# PIR_Part_V_1.net
KiCad netlist of a schematic drawn in Altium Designer
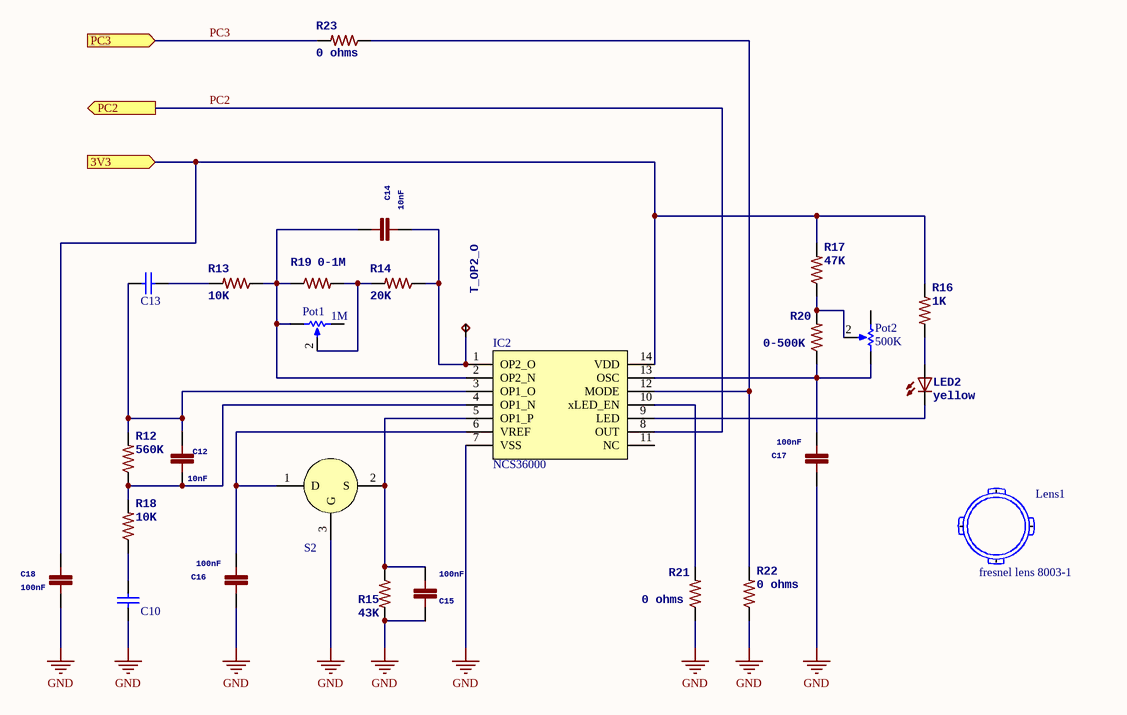
[diagram p0: PIR_Part_V.1.SchDoc]

(export (version "E")
  (design (tool "Eeschema 10.0.6"))
  (components
    (comp (ref "C10")
      (value "33uF")
      (footprint "Axsem-PIR_V.1:C1206")
      (description "C1206")
      (libsource (lib "Axsem-PIR_V.1") (part "C1206"))
    )
    (comp (ref "C12") (value "10nF") (footprint "Axsem-PIR_V.1:C0402") (libsource (lib "") (part "C0402_2")))
    (comp (ref "C13")
      (value "33uF")
      (footprint "Axsem-PIR_V.1:C1206")
      (description "C1206")
      (libsource (lib "Axsem-PIR_V.1") (part "C1206"))
    )
    (comp (ref "C14") (value "10nF") (footprint "Axsem-PIR_V.1:C0402") (libsource (lib "") (part "C0402_1")))
    (comp (ref "C15")
      (value "100nF")
      (footprint "Axsem-PIR_V.1:C0402")
      (libsource (lib "Axsem-PIR_V.1") (part "C0402"))
    )
    (comp (ref "C16") (value "100nF") (footprint "C0402") (libsource (lib "Axsem-PIR_V.1") (part "C0402")))
    (comp (ref "C17") (value "100nF") (footprint "C0402") (libsource (lib "Axsem-PIR_V.1") (part "C0402")))
    (comp (ref "C18")
      (value "100nF")
      (footprint "C0603")
      (description "C0603")
      (libsource (lib "Axsem-PIR_V.1") (part "C0603"))
    )
    (comp (ref "IC2")
      (value "NCS36000")
      (footprint "SOIC127P600X175-14AN")
      (description "PIR sensor")
      (fields (field (name "MANUFACTURER") "ON semiconductor"))
      (libsource (lib "Axsem-PIR_V.1") (part "NCS36000"))
    )
    (comp (ref "LED2")
      (value "yellow")
      (footprint "LED0603 - Y")
      (description "LED0603-Y")
      (libsource (lib "Axsem-PIR_V.1") (part "LED0603 yellow"))
    )
    (comp (ref "Lens1")
      (value "fresnel lens 8003-1")
      (footprint "Axsem-PIR_V.1:Lens")
      (description "Fresnel Lens 8003-1")
      (libsource (lib "Axsem-PIR_V.1") (part "PIR Fresnel Lens 8003-1"))
    )
    (comp (ref "Pot1")
      (value "1M")
      (footprint "Poti-4mm SMD")
      (description "Bourns 3364W SMD 4mm square Trimpot")
      (libsource (lib "Axsem-PIR_V.1") (part "Trimpot SMD"))
    )
    (comp (ref "Pot2")
      (value "500K")
      (footprint "Poti-4mm SMD")
      (description "Bourns 3364W SMD 4mm square Trimpot")
      (libsource (lib "Axsem-PIR_V.1") (part "Trimpot SMD"))
    )
    (comp (ref "R12") (value "560K") (footprint "R0402") (libsource (lib "Axsem-PIR_V.1") (part "R0402")))
    (comp (ref "R13") (value "10K") (footprint "R0402") (libsource (lib "Axsem-PIR_V.1") (part "R0402")))
    (comp (ref "R14") (value "20K") (footprint "R0402") (libsource (lib "Axsem-PIR_V.1") (part "R0402")))
    (comp (ref "R15") (value "43K") (footprint "R0402") (libsource (lib "Axsem-PIR_V.1") (part "R0402")))
    (comp (ref "R16") (value "1K") (footprint "R0402") (libsource (lib "Axsem-PIR_V.1") (part "R0402")))
    (comp (ref "R17") (value "47K") (footprint "R0402") (libsource (lib "Axsem-PIR_V.1") (part "R0402")))
    (comp (ref "R18") (value "10K") (footprint "R0402") (libsource (lib "Axsem-PIR_V.1") (part "R0402")))
    (comp (ref "R19") (value "0-1M") (footprint "R0402") (libsource (lib "Axsem-PIR_V.1") (part "R0402")))
    (comp (ref "R20") (value "0-500K") (footprint "R0402") (libsource (lib "Axsem-PIR_V.1") (part "R0402")))
    (comp (ref "R21") (value "0 ohms") (footprint "R0402") (libsource (lib "Axsem-PIR_V.1") (part "R0402")))
    (comp (ref "R22") (value "0 ohms") (footprint "R0402") (libsource (lib "Axsem-PIR_V.1") (part "R0402")))
    (comp (ref "R23") (value "0 ohms") (footprint "R0402") (libsource (lib "Axsem-PIR_V.1") (part "R0402")))
    (comp (ref "S2")
      (value "D203S")
      (footprint "ONSC-TO-5-3")
      (description "PIR sensor")
      (fields (field (name "MANUFACTURER") "PIR sensor CO.,LTD"))
      (libsource (lib "Axsem-PIR_V.1") (part "D203S PIR sensor"))
    )
    (comp (ref "T_OP2_O")
      (value "TP03")
      (footprint "PIN-03")
      (description "Test pad")
      (libsource (lib "Axsem-PIR_V.1") (part "TP03"))
    )
  )
  (nets
    (net (code "1") (name "/3V3") (class "Default")
      (node (ref "C18") (pin "2") (pinfunction "2_2") (pintype "passive"))
      (node (ref "IC2") (pin "14") (pinfunction "VDD_14") (pintype "passive"))
      (node (ref "R16") (pin "1") (pinfunction "1_1") (pintype "passive"))
      (node (ref "R17") (pin "2") (pinfunction "2_2") (pintype "passive"))
    )
    (net (code "2") (name "/PC2") (class "Default")
      (node (ref "IC2") (pin "8") (pinfunction "OUT_8") (pintype "passive"))
    )
    (net (code "3") (name "/PC3") (class "Default")
      (node (ref "R23") (pin "2") (pinfunction "2_2") (pintype "passive"))
    )
    (net (code "4") (name "GND") (class "Default")
      (node (ref "C10") (pin "1") (pinfunction "1_1") (pintype "passive"))
      (node (ref "C15") (pin "1") (pinfunction "1_1") (pintype "passive"))
      (node (ref "C16") (pin "1") (pinfunction "1_1") (pintype "passive"))
      (node (ref "C17") (pin "1") (pinfunction "1_1") (pintype "passive"))
      (node (ref "C18") (pin "1") (pinfunction "1_1") (pintype "passive"))
      (node (ref "IC2") (pin "7") (pinfunction "VSS_7") (pintype "passive"))
      (node (ref "R15") (pin "2") (pinfunction "2_2") (pintype "passive"))
      (node (ref "R21") (pin "1") (pinfunction "1_1") (pintype "passive"))
      (node (ref "R22") (pin "1") (pinfunction "1_1") (pintype "passive"))
      (node (ref "S2") (pin "3") (pinfunction "G_3") (pintype "passive"))
    )
    (net (code "5") (name "Net-(C10-Pad2)") (class "Default")
      (node (ref "C10") (pin "2") (pinfunction "2_2") (pintype "passive"))
      (node (ref "R18") (pin "1") (pinfunction "1_1") (pintype "passive"))
    )
    (net (code "6") (name "Net-(C13-Pad1)") (class "Default")
      (node (ref "C13") (pin "1") (pinfunction "1_1") (pintype "passive"))
      (node (ref "R13") (pin "2") (pinfunction "2_2") (pintype "passive"))
    )
    (net (code "7") (name "Net-(IC2-LED)") (class "Default")
      (node (ref "IC2") (pin "9") (pinfunction "LED_9") (pintype "passive"))
      (node (ref "LED2") (pin "C") (pinfunction "C_C") (pintype "passive"))
    )
    (net (code "8") (name "Net-(IC2-MODE)") (class "Default")
      (node (ref "IC2") (pin "12") (pinfunction "MODE_12") (pintype "passive"))
      (node (ref "R22") (pin "2") (pinfunction "2_2") (pintype "passive"))
      (node (ref "R23") (pin "1") (pinfunction "1_1") (pintype "passive"))
    )
    (net (code "9") (name "Net-(IC2-OP1_N)") (class "Default")
      (node (ref "C12") (pin "2") (pinfunction "2_2") (pintype "passive"))
      (node (ref "IC2") (pin "4") (pinfunction "OP1_N_4") (pintype "passive"))
      (node (ref "R12") (pin "1") (pinfunction "1_1") (pintype "passive"))
      (node (ref "R18") (pin "2") (pinfunction "2_2") (pintype "passive"))
    )
    (net (code "10") (name "Net-(IC2-OP1_O)") (class "Default")
      (node (ref "C12") (pin "1") (pinfunction "1_1") (pintype "passive"))
      (node (ref "C13") (pin "2") (pinfunction "2_2") (pintype "passive"))
      (node (ref "IC2") (pin "3") (pinfunction "OP1_O_3") (pintype "passive"))
      (node (ref "R12") (pin "2") (pinfunction "2_2") (pintype "passive"))
    )
    (net (code "11") (name "Net-(IC2-OP1_P)") (class "Default")
      (node (ref "C15") (pin "2") (pinfunction "2_2") (pintype "passive"))
      (node (ref "IC2") (pin "5") (pinfunction "OP1_P_5") (pintype "passive"))
      (node (ref "R15") (pin "1") (pinfunction "1_1") (pintype "passive"))
      (node (ref "S2") (pin "2") (pinfunction "S_2") (pintype "passive"))
    )
    (net (code "12") (name "Net-(IC2-OP2_N)") (class "Default")
      (node (ref "C14") (pin "1") (pinfunction "1_1") (pintype "passive"))
      (node (ref "IC2") (pin "2") (pinfunction "OP2_N_2") (pintype "passive"))
      (node (ref "Pot1") (pin "1") (pinfunction "1_1") (pintype "passive"))
      (node (ref "R13") (pin "1") (pinfunction "1_1") (pintype "passive"))
      (node (ref "R19") (pin "1") (pinfunction "1_1") (pintype "passive"))
    )
    (net (code "13") (name "Net-(IC2-OP2_O)") (class "Default")
      (node (ref "C14") (pin "2") (pinfunction "2_2") (pintype "passive"))
      (node (ref "IC2") (pin "1") (pinfunction "OP2_O_1") (pintype "passive"))
      (node (ref "R14") (pin "1") (pinfunction "1_1") (pintype "passive"))
      (node (ref "T_OP2_O") (pin "P$1") (pinfunction "TP_P$1") (pintype "passive"))
    )
    (net (code "14") (name "Net-(IC2-OSC)") (class "Default")
      (node (ref "C17") (pin "2") (pinfunction "2_2") (pintype "passive"))
      (node (ref "IC2") (pin "13") (pinfunction "OSC_13") (pintype "passive"))
      (node (ref "Pot2") (pin "3") (pinfunction "3_3") (pintype "passive"))
      (node (ref "R20") (pin "1") (pinfunction "1_1") (pintype "passive"))
    )
    (net (code "15") (name "Net-(IC2-VREF)") (class "Default")
      (node (ref "C16") (pin "2") (pinfunction "2_2") (pintype "passive"))
      (node (ref "IC2") (pin "6") (pinfunction "VREF_6") (pintype "passive"))
      (node (ref "S2") (pin "1") (pinfunction "D_1") (pintype "passive"))
    )
    (net (code "16") (name "Net-(IC2-xLED_EN)") (class "Default")
      (node (ref "IC2") (pin "10") (pinfunction "xLED_EN_10") (pintype "passive"))
      (node (ref "R21") (pin "2") (pinfunction "2_2") (pintype "passive"))
    )
    (net (code "17") (name "Net-(LED2-PadA)") (class "Default")
      (node (ref "LED2") (pin "A") (pinfunction "A_A") (pintype "passive"))
      (node (ref "R16") (pin "2") (pinfunction "2_2") (pintype "passive"))
    )
    (net (code "18") (name "Net-(Pot1-Pad2)") (class "Default")
      (node (ref "Pot1") (pin "2") (pinfunction "2_2") (pintype "passive"))
      (node (ref "R14") (pin "2") (pinfunction "2_2") (pintype "passive"))
      (node (ref "R19") (pin "2") (pinfunction "2_2") (pintype "passive"))
    )
    (net (code "19") (name "Net-(Pot2-Pad2)") (class "Default")
      (node (ref "Pot2") (pin "2") (pinfunction "2_2") (pintype "passive"))
      (node (ref "R17") (pin "1") (pinfunction "1_1") (pintype "passive"))
      (node (ref "R20") (pin "2") (pinfunction "2_2") (pintype "passive"))
    )
    (net (code "20") (name "unconnected-(IC2-NC-Pad11)") (class "Default")
      (node (ref "IC2") (pin "11") (pinfunction "NC_11") (pintype "passive"))
    )
    (net (code "21") (name "unconnected-(Lens1-PadTab1)") (class "Default")
      (node (ref "Lens1") (pin "Tab1") (pinfunction "Tab1_Tab1") (pintype "passive"))
    )
    (net (code "22") (name "unconnected-(Lens1-PadTab2)") (class "Default")
      (node (ref "Lens1") (pin "Tab2") (pinfunction "Tab2_Tab2") (pintype "passive"))
    )
    (net (code "23") (name "unconnected-(Lens1-PadTab3)") (class "Default")
      (node (ref "Lens1") (pin "Tab3") (pinfunction "Tab3_Tab3") (pintype "passive"))
    )
    (net (code "24") (name "unconnected-(Lens1-PadTab4)") (class "Default")
      (node (ref "Lens1") (pin "Tab4") (pinfunction "Tab4_Tab4") (pintype "passive"))
    )
    (net (code "25") (name "unconnected-(Pot1-Pad3)") (class "Default")
      (node (ref "Pot1") (pin "3") (pinfunction "3_3") (pintype "passive"))
    )
    (net (code "26") (name "unconnected-(Pot2-Pad1)") (class "Default")
      (node (ref "Pot2") (pin "1") (pinfunction "1_1") (pintype "passive"))
    )
  )
)
